# H14RA.net
KiCad netlist of a schematic drawn in EAGLE
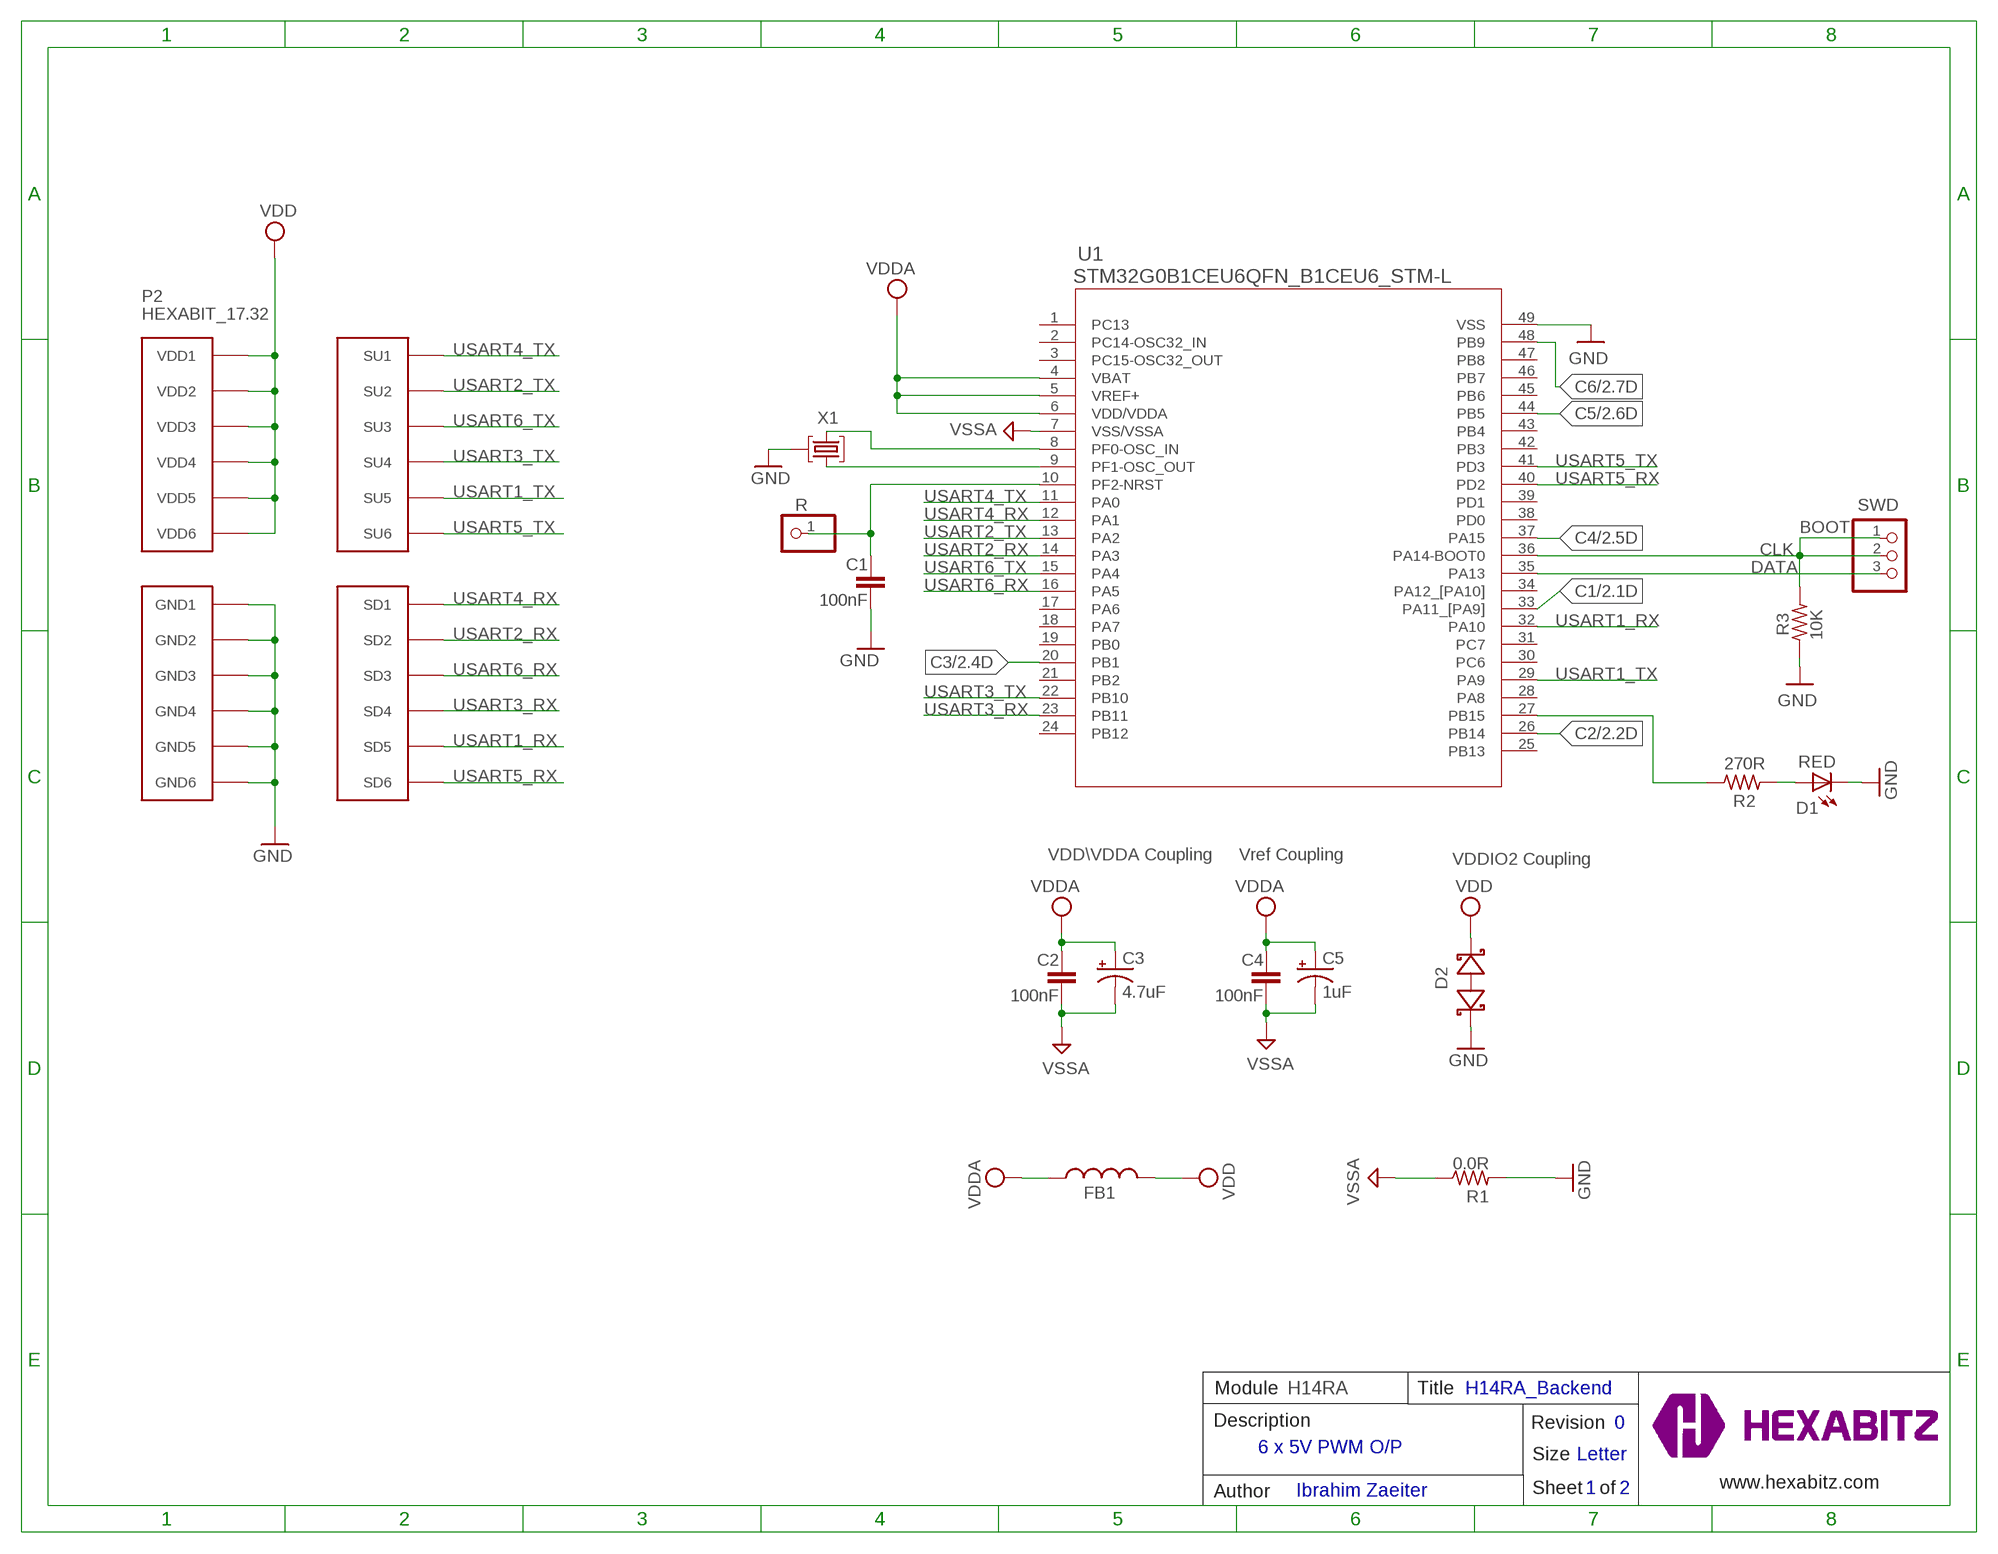
[diagram p0: schematic, sheet 1]
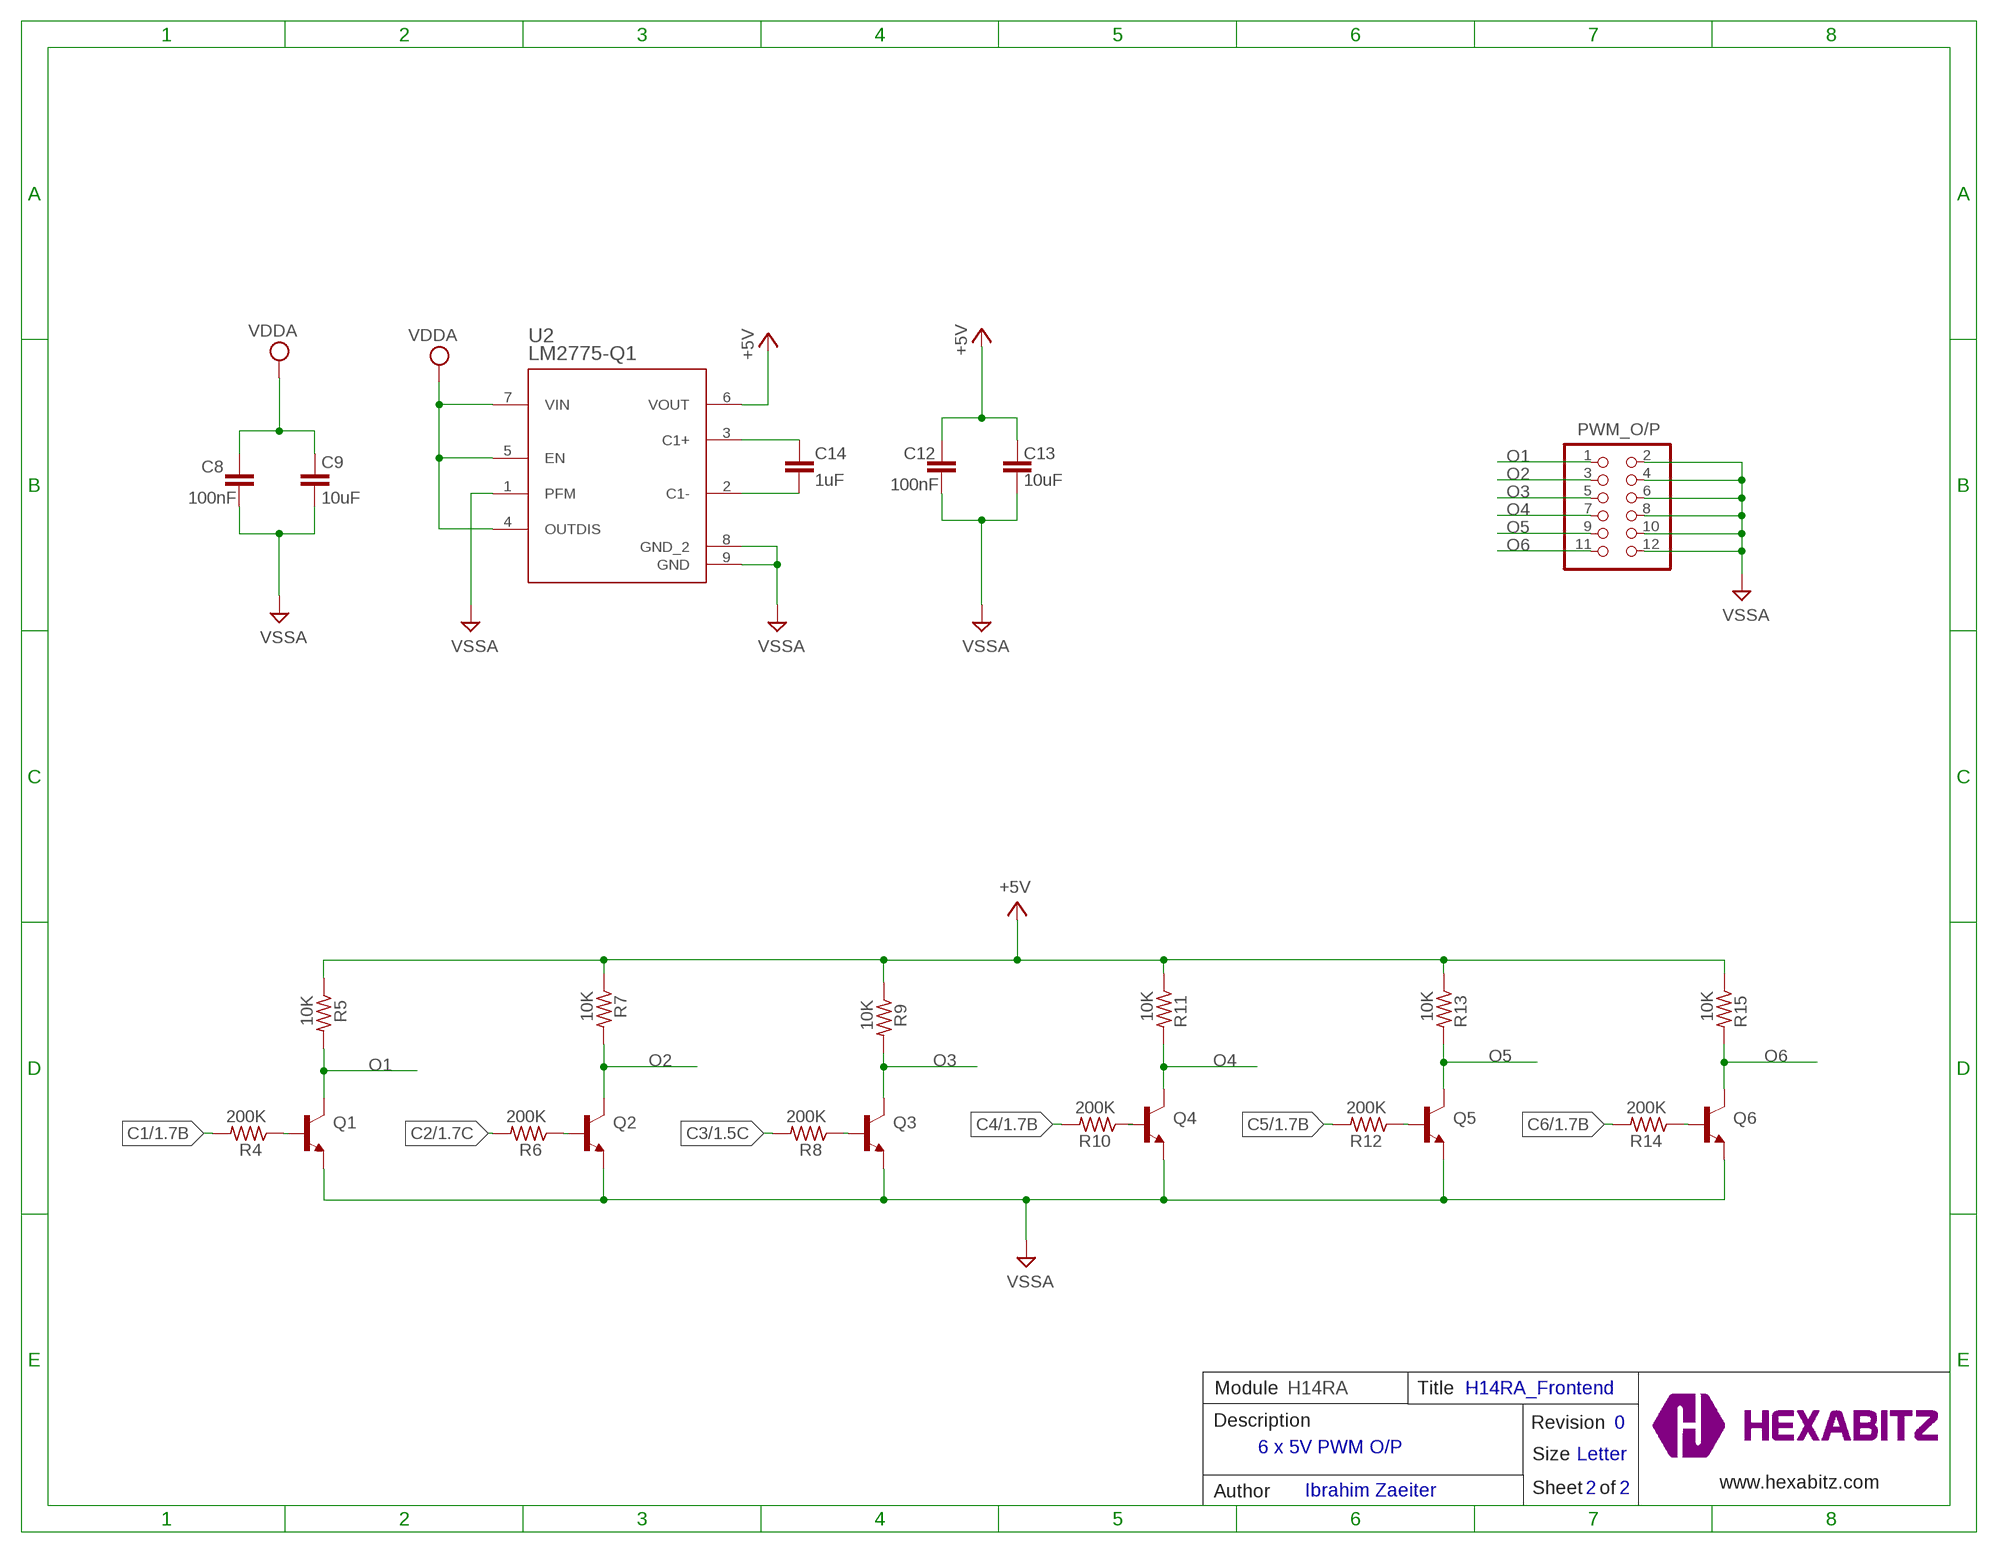
[diagram p1: schematic, sheet 2]

(export (version "E")
  (design (tool "Eeschema 10.0.6"))
  (components
    (comp (ref "C1")
      (value "100nF")
      (footprint "eagle-import:C-0603")
      (libsource (lib "eagle-import") (part "C-0603"))
    )
    (comp (ref "C2")
      (value "100nF")
      (footprint "eagle-import:C-0603")
      (libsource (lib "eagle-import") (part "C-0603"))
    )
    (comp (ref "C3")
      (value "4.7uF")
      (footprint "eagle-import:C-0805-POL")
      (libsource (lib "eagle-import") (part "C-0805-POL"))
    )
    (comp (ref "C4")
      (value "100nF")
      (footprint "eagle-import:C-0603")
      (libsource (lib "eagle-import") (part "C-0603"))
    )
    (comp (ref "C5")
      (value "1uF")
      (footprint "eagle-import:C-0805-POL")
      (libsource (lib "eagle-import") (part "C-0805-POL"))
    )
    (comp (ref "D1")
      (value "RED")
      (footprint "eagle-import:VLMS1300-GS08")
      (fields
        (field (name "MPN") "VLMS1300-GS08")
        (field (name "MFN") "Vishay")
        (field (name "MPN_1") "VLMS1300-GS08")
        (field (name "OCTOPART_URL") "https://octopart.com/vlms1300-gs08-vishay-21709201?r=sp&s=_gcP4_q8T1SC6PJQPTQ9yA")
      )
      (libsource (lib "eagle-import") (part "VLMS1300-GS08"))
    )
    (comp (ref "D2")
      (value "BOURNS_CDSOD323-T03SCBOURNS_CDSOD323-T03SC_0_0")
      (footprint "eagle-import:BOURNS_CDSOD323-T03SC_0")
      (fields (field (name "MPN") "CDSOD323-T03SC"))
      (libsource (lib "eagle-import") (part "BOURNS_CDSOD323-T03SCBOURNS_CDSOD323-T03SC_0_0"))
    )
    (comp (ref "FB1")
      (value "FB-0603")
      (footprint "eagle-import:FB-0603")
      (libsource (lib "eagle-import") (part "FB-0603"))
    )
    (comp (ref "P2")
      (value "HEXABIT_17.32")
      (footprint "eagle-import:HEXABIT_17.32")
      (libsource (lib "eagle-import") (part "HEXABIT_?17.32"))
    )
    (comp (ref "R")
      (value "R")
      (footprint "eagle-import:1X01")
      (fields (field (name "MPN") "87227-1"))
      (libsource (lib "eagle-import") (part "PINHD-1X1"))
    )
    (comp (ref "R1")
      (value "0.0R")
      (footprint "eagle-import:R-0603")
      (libsource (lib "eagle-import") (part "R-0603"))
    )
    (comp (ref "R2")
      (value "270R")
      (footprint "eagle-import:R-0603")
      (libsource (lib "eagle-import") (part "R-0603"))
    )
    (comp (ref "R3")
      (value "10K")
      (footprint "eagle-import:R-0603")
      (libsource (lib "eagle-import") (part "R-0603"))
    )
    (comp (ref "SWD")
      (value "PINHD-1X3")
      (footprint "eagle-import:1X03")
      (libsource (lib "eagle-import") (part "PINHD-1X3"))
    )
    (comp (ref "TRIMBLE-LOGO2")
      (value "HEXA-LOGO")
      (footprint "eagle-import:HEXA-LOGO")
      (libsource (lib "eagle-import") (part "HEXA-LOGO"))
    )
    (comp (ref "U1")
      (value "STM32G0B1CEU6QFN_B1CEU6_STM-L")
      (footprint "eagle-import:QFN_B1CEU6_STM-L")
      (fields
        (field (name "MANUFACTURER_PART_NUMBER") "STM32G0B1CEU6")
        (field (name "COPYRIGHT") "Copyright (C) 2021 Ultra Librarian. All rights reserved.")
      )
      (libsource (lib "eagle-import") (part "STM32G0B1CEU6QFN_B1CEU6_STM-L"))
    )
    (comp (ref "X1")
      (value "XTALL_CSTCE8M00G52")
      (footprint "eagle-import:XTALL_CSTCE8M00G52")
      (fields (field (name "MPN") "CSTCE8M00G52Z-R0"))
      (libsource (lib "eagle-import") (part "XTALL_CSTCE8M00G52"))
    )
    (comp (ref "C8")
      (value "100nF")
      (footprint "eagle-import:C-0603")
      (libsource (lib "eagle-import") (part "C-0603"))
    )
    (comp (ref "C9")
      (value "10uF")
      (footprint "eagle-import:C-0603")
      (libsource (lib "eagle-import") (part "C-0603"))
    )
    (comp (ref "C12")
      (value "100nF")
      (footprint "eagle-import:C-0603")
      (libsource (lib "eagle-import") (part "C-0603"))
    )
    (comp (ref "C13")
      (value "10uF")
      (footprint "eagle-import:C-0603")
      (libsource (lib "eagle-import") (part "C-0603"))
    )
    (comp (ref "C14")
      (value "1uF")
      (footprint "eagle-import:C-0805")
      (libsource (lib "eagle-import") (part "C-0805"))
    )
    (comp (ref "PWM_O/P")
      (value "PINHD-2X6")
      (footprint "eagle-import:2X06")
      (libsource (lib "eagle-import") (part "PINHD-2X6"))
    )
    (comp (ref "Q1")
      (value "MMBT3904LT1")
      (footprint "eagle-import:MMBT3904LT1")
      (libsource (lib "eagle-import") (part "MMBT3904LT1"))
    )
    (comp (ref "Q2")
      (value "MMBT3904LT1")
      (footprint "eagle-import:MMBT3904LT1")
      (libsource (lib "eagle-import") (part "MMBT3904LT1"))
    )
    (comp (ref "Q3")
      (value "MMBT3904LT1")
      (footprint "eagle-import:MMBT3904LT1")
      (libsource (lib "eagle-import") (part "MMBT3904LT1"))
    )
    (comp (ref "Q4")
      (value "MMBT3904LT1")
      (footprint "eagle-import:MMBT3904LT1")
      (libsource (lib "eagle-import") (part "MMBT3904LT1"))
    )
    (comp (ref "Q5")
      (value "MMBT3904LT1")
      (footprint "eagle-import:MMBT3904LT1")
      (libsource (lib "eagle-import") (part "MMBT3904LT1"))
    )
    (comp (ref "Q6")
      (value "MMBT3904LT1")
      (footprint "eagle-import:MMBT3904LT1")
      (libsource (lib "eagle-import") (part "MMBT3904LT1"))
    )
    (comp (ref "R4")
      (value "200K")
      (footprint "eagle-import:R-0603")
      (libsource (lib "eagle-import") (part "R-0603"))
    )
    (comp (ref "R5")
      (value "10K")
      (footprint "eagle-import:R-0603")
      (libsource (lib "eagle-import") (part "R-0603"))
    )
    (comp (ref "R6")
      (value "200K")
      (footprint "eagle-import:R-0603")
      (libsource (lib "eagle-import") (part "R-0603"))
    )
    (comp (ref "R7")
      (value "10K")
      (footprint "eagle-import:R-0603")
      (libsource (lib "eagle-import") (part "R-0603"))
    )
    (comp (ref "R8")
      (value "200K")
      (footprint "eagle-import:R-0603")
      (libsource (lib "eagle-import") (part "R-0603"))
    )
    (comp (ref "R9")
      (value "10K")
      (footprint "eagle-import:R-0603")
      (libsource (lib "eagle-import") (part "R-0603"))
    )
    (comp (ref "R10")
      (value "200K")
      (footprint "eagle-import:R-0603")
      (libsource (lib "eagle-import") (part "R-0603"))
    )
    (comp (ref "R11")
      (value "10K")
      (footprint "eagle-import:R-0603")
      (libsource (lib "eagle-import") (part "R-0603"))
    )
    (comp (ref "R12")
      (value "200K")
      (footprint "eagle-import:R-0603")
      (libsource (lib "eagle-import") (part "R-0603"))
    )
    (comp (ref "R13")
      (value "10K")
      (footprint "eagle-import:R-0603")
      (libsource (lib "eagle-import") (part "R-0603"))
    )
    (comp (ref "R14")
      (value "200K")
      (footprint "eagle-import:R-0603")
      (libsource (lib "eagle-import") (part "R-0603"))
    )
    (comp (ref "R15")
      (value "10K")
      (footprint "eagle-import:R-0603")
      (libsource (lib "eagle-import") (part "R-0603"))
    )
    (comp (ref "U2")
      (value "LM2775-Q1")
      (footprint "eagle-import:DSG0008A")
      (fields (field (name "MANUFACTURER") "Texas Instruments") (field (name "MPN") "LM2775QDSGRQ1"))
      (libsource (lib "eagle-import") (part "LM2775QDSGRQ1"))
    )
  )
  (nets
    (net (code "1") (name "+5V") (class "Default")
      (node (ref "C12") (pin "1") (pinfunction "1_1") (pintype "passive"))
      (node (ref "C13") (pin "1") (pinfunction "1_1") (pintype "passive"))
      (node (ref "R11") (pin "1") (pinfunction "1_1") (pintype "passive"))
      (node (ref "R13") (pin "1") (pinfunction "1_1") (pintype "passive"))
      (node (ref "R15") (pin "1") (pinfunction "1_1") (pintype "passive"))
      (node (ref "R5") (pin "1") (pinfunction "1_1") (pintype "passive"))
      (node (ref "R7") (pin "1") (pinfunction "1_1") (pintype "passive"))
      (node (ref "R9") (pin "1") (pinfunction "1_1") (pintype "passive"))
      (node (ref "U2") (pin "6") (pinfunction "VOUT_6") (pintype "power_in"))
    )
    (net (code "2") (name "C1") (class "Default")
      (node (ref "R4") (pin "2") (pinfunction "2_2") (pintype "passive"))
      (node (ref "U1") (pin "33") (pinfunction "PA11_[PA9]_33") (pintype "bidirectional"))
    )
    (net (code "3") (name "C2") (class "Default")
      (node (ref "R6") (pin "2") (pinfunction "2_2") (pintype "passive"))
      (node (ref "U1") (pin "26") (pinfunction "PB14_26") (pintype "bidirectional"))
    )
    (net (code "4") (name "C3") (class "Default")
      (node (ref "R8") (pin "2") (pinfunction "2_2") (pintype "passive"))
      (node (ref "U1") (pin "20") (pinfunction "PB1_20") (pintype "bidirectional"))
    )
    (net (code "5") (name "C4") (class "Default")
      (node (ref "R10") (pin "2") (pinfunction "2_2") (pintype "passive"))
      (node (ref "U1") (pin "37") (pinfunction "PA15_37") (pintype "bidirectional"))
    )
    (net (code "6") (name "C5") (class "Default")
      (node (ref "R12") (pin "2") (pinfunction "2_2") (pintype "passive"))
      (node (ref "U1") (pin "44") (pinfunction "PB5_44") (pintype "bidirectional"))
    )
    (net (code "7") (name "C6") (class "Default")
      (node (ref "R14") (pin "2") (pinfunction "2_2") (pintype "passive"))
      (node (ref "U1") (pin "48") (pinfunction "PB9_48") (pintype "bidirectional"))
    )
    (net (code "8") (name "CLK") (class "Default")
      (node (ref "R3") (pin "2") (pinfunction "2_2") (pintype "passive"))
      (node (ref "SWD") (pin "1") (pinfunction "1_1") (pintype "passive"))
      (node (ref "SWD") (pin "2") (pinfunction "2_2") (pintype "passive"))
      (node (ref "U1") (pin "36") (pinfunction "PA14-BOOT0_36") (pintype "bidirectional"))
    )
    (net (code "9") (name "DATA") (class "Default")
      (node (ref "SWD") (pin "3") (pinfunction "3_3") (pintype "passive"))
      (node (ref "U1") (pin "35") (pinfunction "PA13_35") (pintype "bidirectional"))
    )
    (net (code "10") (name "GND") (class "Default")
      (node (ref "C1") (pin "2") (pinfunction "2_2") (pintype "passive"))
      (node (ref "D1") (pin "C") (pinfunction "C_C") (pintype "passive"))
      (node (ref "D2") (pin "1") (pinfunction "A_1") (pintype "passive"))
      (node (ref "P2") (pin "PAD_PD10") (pinfunction "GND4_PAD_PD10") (pintype "power_in"))
      (node (ref "P2") (pin "PAD_PD11") (pinfunction "GND5_PAD_PD11") (pintype "power_in"))
      (node (ref "P2") (pin "PAD_PD12") (pinfunction "GND6_PAD_PD12") (pintype "power_in"))
      (node (ref "P2") (pin "PAD_PD7") (pinfunction "GND1_PAD_PD7") (pintype "power_in"))
      (node (ref "P2") (pin "PAD_PD8") (pinfunction "GND2_PAD_PD8") (pintype "power_in"))
      (node (ref "P2") (pin "PAD_PD9") (pinfunction "GND3_PAD_PD9") (pintype "power_in"))
      (node (ref "R1") (pin "2") (pinfunction "2_2") (pintype "passive"))
      (node (ref "R3") (pin "1") (pinfunction "1_1") (pintype "passive"))
      (node (ref "U1") (pin "49") (pinfunction "VSS_49") (pintype "passive"))
      (node (ref "X1") (pin "P$2") (pinfunction "2_P$2") (pintype "passive"))
    )
    (net (code "11") (name "Net-(D1-PadA)") (class "Default")
      (node (ref "D1") (pin "A") (pinfunction "A_A") (pintype "passive"))
      (node (ref "R2") (pin "2") (pinfunction "2_2") (pintype "passive"))
    )
    (net (code "12") (name "Net-(Q1-B)") (class "Default")
      (node (ref "Q1") (pin "1") (pinfunction "B_1") (pintype "passive"))
      (node (ref "R4") (pin "1") (pinfunction "1_1") (pintype "passive"))
    )
    (net (code "13") (name "Net-(Q2-B)") (class "Default")
      (node (ref "Q2") (pin "1") (pinfunction "B_1") (pintype "passive"))
      (node (ref "R6") (pin "1") (pinfunction "1_1") (pintype "passive"))
    )
    (net (code "14") (name "Net-(Q3-B)") (class "Default")
      (node (ref "Q3") (pin "1") (pinfunction "B_1") (pintype "passive"))
      (node (ref "R8") (pin "1") (pinfunction "1_1") (pintype "passive"))
    )
    (net (code "15") (name "Net-(Q4-B)") (class "Default")
      (node (ref "Q4") (pin "1") (pinfunction "B_1") (pintype "passive"))
      (node (ref "R10") (pin "1") (pinfunction "1_1") (pintype "passive"))
    )
    (net (code "16") (name "Net-(Q5-B)") (class "Default")
      (node (ref "Q5") (pin "1") (pinfunction "B_1") (pintype "passive"))
      (node (ref "R12") (pin "1") (pinfunction "1_1") (pintype "passive"))
    )
    (net (code "17") (name "Net-(Q6-B)") (class "Default")
      (node (ref "Q6") (pin "1") (pinfunction "B_1") (pintype "passive"))
      (node (ref "R14") (pin "1") (pinfunction "1_1") (pintype "passive"))
    )
    (net (code "18") (name "Net-(U1-PB15)") (class "Default")
      (node (ref "R2") (pin "1") (pinfunction "1_1") (pintype "passive"))
      (node (ref "U1") (pin "27") (pinfunction "PB15_27") (pintype "bidirectional"))
    )
    (net (code "19") (name "Net-(U1-PF0-OSC_IN)") (class "Default")
      (node (ref "U1") (pin "8") (pinfunction "PF0-OSC_IN_8") (pintype "bidirectional"))
      (node (ref "X1") (pin "P$3") (pinfunction "3_P$3") (pintype "passive"))
    )
    (net (code "20") (name "Net-(U1-PF1-OSC_OUT)") (class "Default")
      (node (ref "U1") (pin "9") (pinfunction "PF1-OSC_OUT_9") (pintype "output"))
      (node (ref "X1") (pin "P$1") (pinfunction "1_P$1") (pintype "passive"))
    )
    (net (code "21") (name "Net-(U1-PF2-NRST)") (class "Default")
      (node (ref "C1") (pin "1") (pinfunction "1_1") (pintype "passive"))
      (node (ref "R") (pin "1") (pinfunction "1_1") (pintype "passive"))
      (node (ref "U1") (pin "10") (pinfunction "PF2-NRST_10") (pintype "bidirectional"))
    )
    (net (code "22") (name "Net-(U2-C1+)") (class "Default")
      (node (ref "C14") (pin "1") (pinfunction "1_1") (pintype "passive"))
      (node (ref "U2") (pin "3") (pinfunction "C1+_3") (pintype "power_in"))
    )
    (net (code "23") (name "Net-(U2-C1-)") (class "Default")
      (node (ref "C14") (pin "2") (pinfunction "2_2") (pintype "passive"))
      (node (ref "U2") (pin "2") (pinfunction "C1-_2") (pintype "power_in"))
    )
    (net (code "24") (name "O1") (class "Default")
      (node (ref "PWM_O/P") (pin "1") (pinfunction "1_1") (pintype "passive"))
      (node (ref "Q1") (pin "3") (pinfunction "C_3") (pintype "passive"))
      (node (ref "R5") (pin "2") (pinfunction "2_2") (pintype "passive"))
    )
    (net (code "25") (name "O2") (class "Default")
      (node (ref "PWM_O/P") (pin "3") (pinfunction "3_3") (pintype "passive"))
      (node (ref "Q2") (pin "3") (pinfunction "C_3") (pintype "passive"))
      (node (ref "R7") (pin "2") (pinfunction "2_2") (pintype "passive"))
    )
    (net (code "26") (name "O3") (class "Default")
      (node (ref "PWM_O/P") (pin "5") (pinfunction "5_5") (pintype "passive"))
      (node (ref "Q3") (pin "3") (pinfunction "C_3") (pintype "passive"))
      (node (ref "R9") (pin "2") (pinfunction "2_2") (pintype "passive"))
    )
    (net (code "27") (name "O4") (class "Default")
      (node (ref "PWM_O/P") (pin "7") (pinfunction "7_7") (pintype "passive"))
      (node (ref "Q4") (pin "3") (pinfunction "C_3") (pintype "passive"))
      (node (ref "R11") (pin "2") (pinfunction "2_2") (pintype "passive"))
    )
    (net (code "28") (name "O5") (class "Default")
      (node (ref "PWM_O/P") (pin "9") (pinfunction "9_9") (pintype "passive"))
      (node (ref "Q5") (pin "3") (pinfunction "C_3") (pintype "passive"))
      (node (ref "R13") (pin "2") (pinfunction "2_2") (pintype "passive"))
    )
    (net (code "29") (name "O6") (class "Default")
      (node (ref "PWM_O/P") (pin "11") (pinfunction "11_11") (pintype "passive"))
      (node (ref "Q6") (pin "3") (pinfunction "C_3") (pintype "passive"))
      (node (ref "R15") (pin "2") (pinfunction "2_2") (pintype "passive"))
    )
    (net (code "30") (name "USART1_RX") (class "Default")
      (node (ref "P2") (pin "PAD_PD5") (pinfunction "SD5_PAD_PD5") (pintype "bidirectional"))
      (node (ref "U1") (pin "32") (pinfunction "PA10_32") (pintype "bidirectional"))
    )
    (net (code "31") (name "USART1_TX") (class "Default")
      (node (ref "P2") (pin "PAD_PU5") (pinfunction "SU5_PAD_PU5") (pintype "bidirectional"))
      (node (ref "U1") (pin "29") (pinfunction "PA9_29") (pintype "bidirectional"))
    )
    (net (code "32") (name "USART2_RX") (class "Default")
      (node (ref "P2") (pin "PAD_PD2") (pinfunction "SD2_PAD_PD2") (pintype "bidirectional"))
      (node (ref "U1") (pin "14") (pinfunction "PA3_14") (pintype "bidirectional"))
    )
    (net (code "33") (name "USART2_TX") (class "Default")
      (node (ref "P2") (pin "PAD_PU2") (pinfunction "SU2_PAD_PU2") (pintype "bidirectional"))
      (node (ref "U1") (pin "13") (pinfunction "PA2_13") (pintype "bidirectional"))
    )
    (net (code "34") (name "USART3_RX") (class "Default")
      (node (ref "P2") (pin "PAD_PD4") (pinfunction "SD4_PAD_PD4") (pintype "bidirectional"))
      (node (ref "U1") (pin "23") (pinfunction "PB11_23") (pintype "bidirectional"))
    )
    (net (code "35") (name "USART3_TX") (class "Default")
      (node (ref "P2") (pin "PAD_PU4") (pinfunction "SU4_PAD_PU4") (pintype "bidirectional"))
      (node (ref "U1") (pin "22") (pinfunction "PB10_22") (pintype "bidirectional"))
    )
    (net (code "36") (name "USART4_RX") (class "Default")
      (node (ref "P2") (pin "PAD_PD1") (pinfunction "SD1_PAD_PD1") (pintype "bidirectional"))
      (node (ref "U1") (pin "12") (pinfunction "PA1_12") (pintype "bidirectional"))
    )
    (net (code "37") (name "USART4_TX") (class "Default")
      (node (ref "P2") (pin "PAD_PU1") (pinfunction "SU1_PAD_PU1") (pintype "bidirectional"))
      (node (ref "U1") (pin "11") (pinfunction "PA0_11") (pintype "bidirectional"))
    )
    (net (code "38") (name "USART5_RX") (class "Default")
      (node (ref "P2") (pin "PAD_PD6") (pinfunction "SD6_PAD_PD6") (pintype "bidirectional"))
      (node (ref "U1") (pin "40") (pinfunction "PD2_40") (pintype "bidirectional"))
    )
    (net (code "39") (name "USART5_TX") (class "Default")
      (node (ref "P2") (pin "PAD_PU6") (pinfunction "SU6_PAD_PU6") (pintype "bidirectional"))
      (node (ref "U1") (pin "41") (pinfunction "PD3_41") (pintype "bidirectional"))
    )
    (net (code "40") (name "USART6_RX") (class "Default")
      (node (ref "P2") (pin "PAD_PD3") (pinfunction "SD3_PAD_PD3") (pintype "bidirectional"))
      (node (ref "U1") (pin "16") (pinfunction "PA5_16") (pintype "bidirectional"))
    )
    (net (code "41") (name "USART6_TX") (class "Default")
      (node (ref "P2") (pin "PAD_PU3") (pinfunction "SU3_PAD_PU3") (pintype "bidirectional"))
      (node (ref "U1") (pin "15") (pinfunction "PA4_15") (pintype "bidirectional"))
    )
    (net (code "42") (name "VDD") (class "Default")
      (node (ref "D2") (pin "2") (pinfunction "C_2") (pintype "passive"))
      (node (ref "FB1") (pin "2") (pinfunction "2_2") (pintype "passive"))
      (node (ref "P2") (pin "PAD_PU10") (pinfunction "VDD4_PAD_PU10") (pintype "power_in"))
      (node (ref "P2") (pin "PAD_PU11") (pinfunction "VDD5_PAD_PU11") (pintype "power_in"))
      (node (ref "P2") (pin "PAD_PU12") (pinfunction "VDD6_PAD_PU12") (pintype "power_in"))
      (node (ref "P2") (pin "PAD_PU7") (pinfunction "VDD1_PAD_PU7") (pintype "power_in"))
      (node (ref "P2") (pin "PAD_PU8") (pinfunction "VDD2_PAD_PU8") (pintype "power_in"))
      (node (ref "P2") (pin "PAD_PU9") (pinfunction "VDD3_PAD_PU9") (pintype "power_in"))
    )
    (net (code "43") (name "VDDA") (class "Default")
      (node (ref "C2") (pin "1") (pinfunction "1_1") (pintype "passive"))
      (node (ref "C3") (pin "1") (pinfunction "+_1") (pintype "passive"))
      (node (ref "C4") (pin "1") (pinfunction "1_1") (pintype "passive"))
      (node (ref "C5") (pin "1") (pinfunction "+_1") (pintype "passive"))
      (node (ref "C8") (pin "1") (pinfunction "1_1") (pintype "passive"))
      (node (ref "C9") (pin "1") (pinfunction "1_1") (pintype "passive"))
      (node (ref "FB1") (pin "1") (pinfunction "1_1") (pintype "passive"))
      (node (ref "U1") (pin "4") (pinfunction "VBAT_4") (pintype "passive"))
      (node (ref "U1") (pin "5") (pinfunction "VREF+_5") (pintype "power_in"))
      (node (ref "U1") (pin "6") (pinfunction "VDD/VDDA_6") (pintype "power_in"))
      (node (ref "U2") (pin "4") (pinfunction "OUTDIS_4") (pintype "input"))
      (node (ref "U2") (pin "5") (pinfunction "EN_5") (pintype "input"))
      (node (ref "U2") (pin "7") (pinfunction "VIN_7") (pintype "power_in"))
    )
    (net (code "44") (name "VSSA") (class "Default")
      (node (ref "C12") (pin "2") (pinfunction "2_2") (pintype "passive"))
      (node (ref "C13") (pin "2") (pinfunction "2_2") (pintype "passive"))
      (node (ref "C2") (pin "2") (pinfunction "2_2") (pintype "passive"))
      (node (ref "C3") (pin "2") (pinfunction "-_2") (pintype "passive"))
      (node (ref "C4") (pin "2") (pinfunction "2_2") (pintype "passive"))
      (node (ref "C5") (pin "2") (pinfunction "-_2") (pintype "passive"))
      (node (ref "C8") (pin "2") (pinfunction "2_2") (pintype "passive"))
      (node (ref "C9") (pin "2") (pinfunction "2_2") (pintype "passive"))
      (node (ref "PWM_O/P") (pin "10") (pinfunction "10_10") (pintype "passive"))
      (node (ref "PWM_O/P") (pin "12") (pinfunction "12_12") (pintype "passive"))
      (node (ref "PWM_O/P") (pin "2") (pinfunction "2_2") (pintype "passive"))
      (node (ref "PWM_O/P") (pin "4") (pinfunction "4_4") (pintype "passive"))
      (node (ref "PWM_O/P") (pin "6") (pinfunction "6_6") (pintype "passive"))
      (node (ref "PWM_O/P") (pin "8") (pinfunction "8_8") (pintype "passive"))
      (node (ref "Q1") (pin "2") (pinfunction "E_2") (pintype "passive"))
      (node (ref "Q2") (pin "2") (pinfunction "E_2") (pintype "passive"))
      (node (ref "Q3") (pin "2") (pinfunction "E_2") (pintype "passive"))
      (node (ref "Q4") (pin "2") (pinfunction "E_2") (pintype "passive"))
      (node (ref "Q5") (pin "2") (pinfunction "E_2") (pintype "passive"))
      (node (ref "Q6") (pin "2") (pinfunction "E_2") (pintype "passive"))
      (node (ref "R1") (pin "1") (pinfunction "1_1") (pintype "passive"))
      (node (ref "U1") (pin "7") (pinfunction "VSS/VSSA_7") (pintype "passive"))
      (node (ref "U2") (pin "1") (pinfunction "PFM_1") (pintype "input"))
      (node (ref "U2") (pin "8") (pinfunction "GND_2_8") (pintype "power_in"))
      (node (ref "U2") (pin "9") (pinfunction "GND_9") (pintype "power_in"))
    )
    (net (code "45") (name "unconnected-(U1-PA6-Pad17)") (class "Default")
      (node (ref "U1") (pin "17") (pinfunction "PA6_17") (pintype "bidirectional"))
    )
    (net (code "46") (name "unconnected-(U1-PA7-Pad18)") (class "Default")
      (node (ref "U1") (pin "18") (pinfunction "PA7_18") (pintype "bidirectional"))
    )
    (net (code "47") (name "unconnected-(U1-PA8-Pad28)") (class "Default")
      (node (ref "U1") (pin "28") (pinfunction "PA8_28") (pintype "bidirectional"))
    )
    (net (code "48") (name "unconnected-(U1-PA12_[PA10]-Pad34)") (class "Default")
      (node (ref "U1") (pin "34") (pinfunction "PA12_[PA10]_34") (pintype "bidirectional"))
    )
    (net (code "49") (name "unconnected-(U1-PB0-Pad19)") (class "Default")
      (node (ref "U1") (pin "19") (pinfunction "PB0_19") (pintype "bidirectional"))
    )
    (net (code "50") (name "unconnected-(U1-PB2-Pad21)") (class "Default")
      (node (ref "U1") (pin "21") (pinfunction "PB2_21") (pintype "bidirectional"))
    )
    (net (code "51") (name "unconnected-(U1-PB3-Pad42)") (class "Default")
      (node (ref "U1") (pin "42") (pinfunction "PB3_42") (pintype "bidirectional"))
    )
    (net (code "52") (name "unconnected-(U1-PB4-Pad43)") (class "Default")
      (node (ref "U1") (pin "43") (pinfunction "PB4_43") (pintype "bidirectional"))
    )
    (net (code "53") (name "unconnected-(U1-PB6-Pad45)") (class "Default")
      (node (ref "U1") (pin "45") (pinfunction "PB6_45") (pintype "bidirectional"))
    )
    (net (code "54") (name "unconnected-(U1-PB7-Pad46)") (class "Default")
      (node (ref "U1") (pin "46") (pinfunction "PB7_46") (pintype "bidirectional"))
    )
    (net (code "55") (name "unconnected-(U1-PB8-Pad47)") (class "Default")
      (node (ref "U1") (pin "47") (pinfunction "PB8_47") (pintype "bidirectional"))
    )
    (net (code "56") (name "unconnected-(U1-PB12-Pad24)") (class "Default")
      (node (ref "U1") (pin "24") (pinfunction "PB12_24") (pintype "bidirectional"))
    )
    (net (code "57") (name "unconnected-(U1-PB13-Pad25)") (class "Default")
      (node (ref "U1") (pin "25") (pinfunction "PB13_25") (pintype "bidirectional"))
    )
    (net (code "58") (name "unconnected-(U1-PC6-Pad30)") (class "Default")
      (node (ref "U1") (pin "30") (pinfunction "PC6_30") (pintype "bidirectional"))
    )
    (net (code "59") (name "unconnected-(U1-PC7-Pad31)") (class "Default")
      (node (ref "U1") (pin "31") (pinfunction "PC7_31") (pintype "bidirectional"))
    )
    (net (code "60") (name "unconnected-(U1-PC13-Pad1)") (class "Default")
      (node (ref "U1") (pin "1") (pinfunction "PC13_1") (pintype "bidirectional"))
    )
    (net (code "61") (name "unconnected-(U1-PC14-OSC32_IN-Pad2)") (class "Default")
      (node (ref "U1") (pin "2") (pinfunction "PC14-OSC32_IN_2") (pintype "bidirectional"))
    )
    (net (code "62") (name "unconnected-(U1-PC15-OSC32_OUT-Pad3)") (class "Default")
      (node (ref "U1") (pin "3") (pinfunction "PC15-OSC32_OUT_3") (pintype "output"))
    )
    (net (code "63") (name "unconnected-(U1-PD0-Pad38)") (class "Default")
      (node (ref "U1") (pin "38") (pinfunction "PD0_38") (pintype "bidirectional"))
    )
    (net (code "64") (name "unconnected-(U1-PD1-Pad39)") (class "Default")
      (node (ref "U1") (pin "39") (pinfunction "PD1_39") (pintype "bidirectional"))
    )
  )
)
